# Wild_FDD_V1_1.net
KiCad netlist of a schematic drawn in Altium Designer
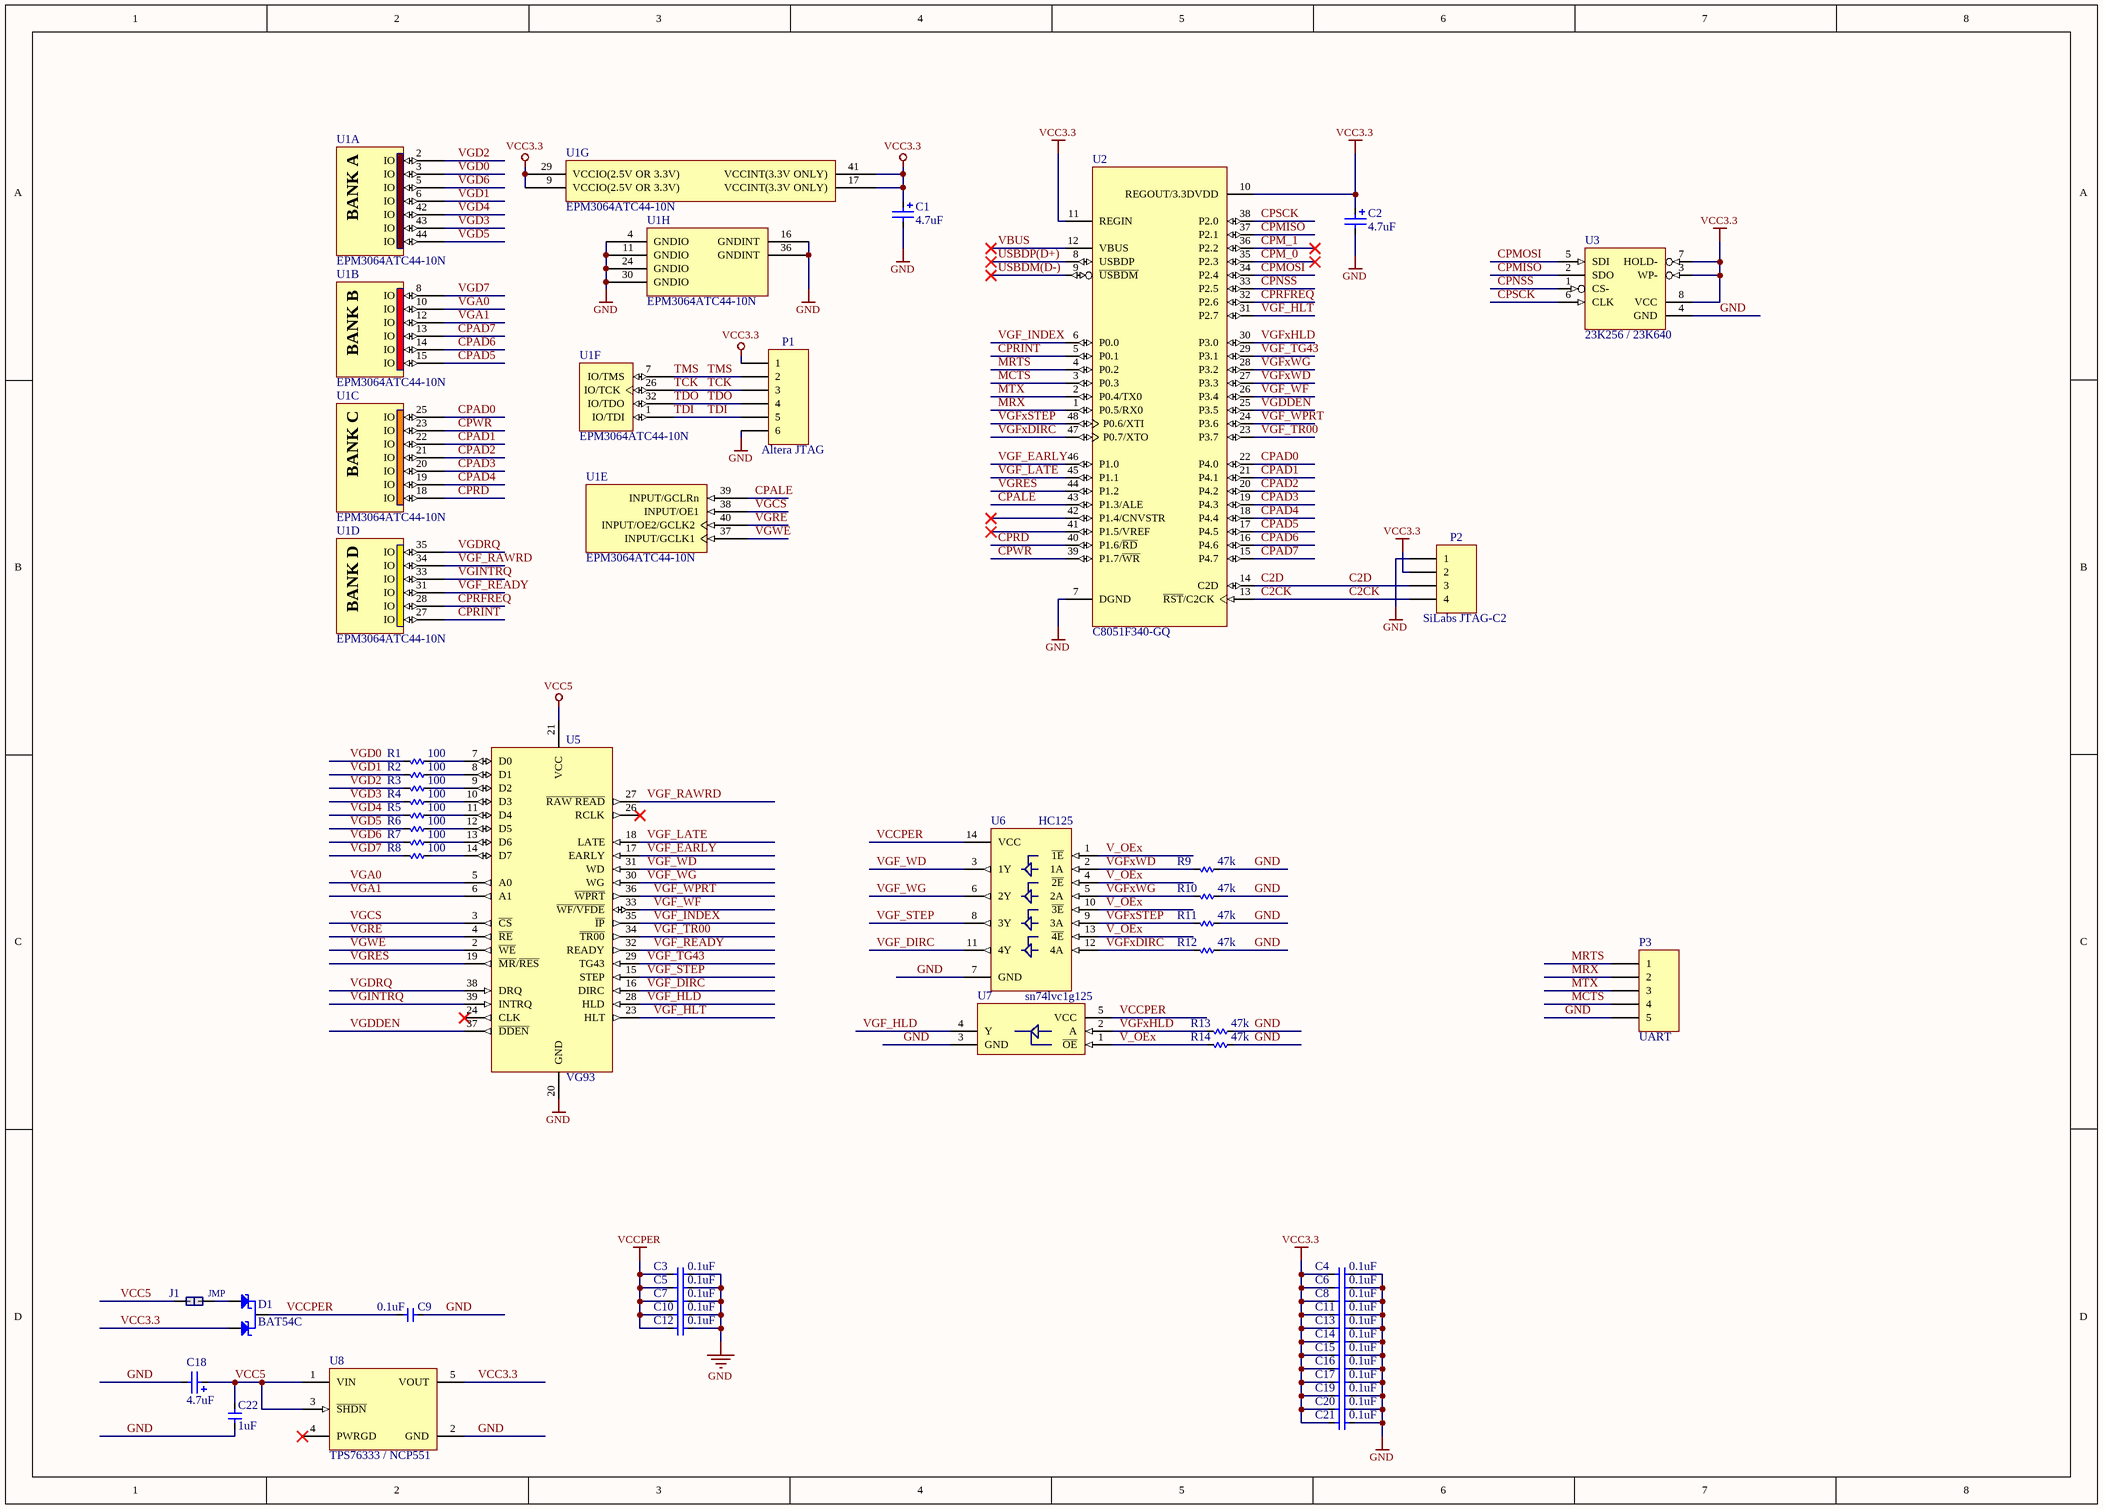
[diagram p0: Wild FDD V1.1.SchDoc]

(export (version "E")
  (design (tool "Eeschema 10.0.6"))
  (components
    (comp (ref "C1")
      (value "4.7uF")
      (footprint "CAP_TAN_B")
      (description "CAP TAN Size C")
      (libsource (lib "IntLib") (part "CAP_TAN_B"))
    )
    (comp (ref "C2")
      (value "4.7uF")
      (footprint "CAP_TAN_B")
      (description "CAP TAN Size C")
      (libsource (lib "IntLib") (part "CAP_TAN_B"))
    )
    (comp (ref "C3")
      (value "0.1uF")
      (footprint "R1005_CAP")
      (description "Capacitor")
      (fields
        (field (name "MANUFACTURER") "Generic Components")
        (field (name "Comment") "CAP")
        (field (name "PUBLISHER") "Altium Limited")
      )
      (libsource (lib "IntLib") (part "CAP"))
    )
    (comp (ref "C4")
      (value "0.1uF")
      (footprint "R1005_CAP")
      (description "Capacitor")
      (fields
        (field (name "MANUFACTURER") "Generic Components")
        (field (name "Comment") "CAP")
        (field (name "PUBLISHER") "Altium Limited")
      )
      (libsource (lib "IntLib") (part "CAP"))
    )
    (comp (ref "C5")
      (value "0.1uF")
      (footprint "R1005_CAP")
      (description "Capacitor")
      (fields
        (field (name "MANUFACTURER") "Generic Components")
        (field (name "Comment") "CAP")
        (field (name "PUBLISHER") "Altium Limited")
      )
      (libsource (lib "IntLib") (part "CAP"))
    )
    (comp (ref "C6")
      (value "0.1uF")
      (footprint "R1005_CAP")
      (description "Capacitor")
      (fields
        (field (name "MANUFACTURER") "Generic Components")
        (field (name "Comment") "CAP")
        (field (name "PUBLISHER") "Altium Limited")
      )
      (libsource (lib "IntLib") (part "CAP"))
    )
    (comp (ref "C7")
      (value "0.1uF")
      (footprint "R1005_CAP")
      (description "Capacitor")
      (fields
        (field (name "MANUFACTURER") "Generic Components")
        (field (name "Comment") "CAP")
        (field (name "PUBLISHER") "Altium Limited")
      )
      (libsource (lib "IntLib") (part "CAP"))
    )
    (comp (ref "C8")
      (value "0.1uF")
      (footprint "R1005_CAP")
      (description "Capacitor")
      (fields
        (field (name "MANUFACTURER") "Generic Components")
        (field (name "Comment") "CAP")
        (field (name "PUBLISHER") "Altium Limited")
      )
      (libsource (lib "IntLib") (part "CAP"))
    )
    (comp (ref "C9")
      (value "0.1uF")
      (footprint "R1005_CAP")
      (description "Capacitor")
      (fields
        (field (name "MANUFACTURER") "Generic Components")
        (field (name "Comment") "CAP")
        (field (name "PUBLISHER") "Altium Limited")
      )
      (libsource (lib "IntLib") (part "CAP"))
    )
    (comp (ref "C10")
      (value "0.1uF")
      (footprint "R1005_CAP")
      (description "Capacitor")
      (fields
        (field (name "MANUFACTURER") "Generic Components")
        (field (name "Comment") "CAP")
        (field (name "PUBLISHER") "Altium Limited")
      )
      (libsource (lib "IntLib") (part "CAP"))
    )
    (comp (ref "C11")
      (value "0.1uF")
      (footprint "R1005_CAP")
      (description "Capacitor")
      (fields
        (field (name "MANUFACTURER") "Generic Components")
        (field (name "Comment") "CAP")
        (field (name "PUBLISHER") "Altium Limited")
      )
      (libsource (lib "IntLib") (part "CAP"))
    )
    (comp (ref "C12")
      (value "0.1uF")
      (footprint "R1005_CAP")
      (description "Capacitor")
      (fields
        (field (name "MANUFACTURER") "Generic Components")
        (field (name "Comment") "CAP")
        (field (name "PUBLISHER") "Altium Limited")
      )
      (libsource (lib "IntLib") (part "CAP"))
    )
    (comp (ref "C13")
      (value "0.1uF")
      (footprint "R1005_CAP")
      (description "Capacitor")
      (fields
        (field (name "MANUFACTURER") "Generic Components")
        (field (name "Comment") "CAP")
        (field (name "PUBLISHER") "Altium Limited")
      )
      (libsource (lib "IntLib") (part "CAP"))
    )
    (comp (ref "C14")
      (value "0.1uF")
      (footprint "R1005_CAP")
      (description "Capacitor")
      (fields
        (field (name "MANUFACTURER") "Generic Components")
        (field (name "Comment") "CAP")
        (field (name "PUBLISHER") "Altium Limited")
      )
      (libsource (lib "IntLib") (part "CAP"))
    )
    (comp (ref "C15")
      (value "0.1uF")
      (footprint "R1005_CAP")
      (description "Capacitor")
      (fields
        (field (name "MANUFACTURER") "Generic Components")
        (field (name "Comment") "CAP")
        (field (name "PUBLISHER") "Altium Limited")
      )
      (libsource (lib "IntLib") (part "CAP"))
    )
    (comp (ref "C16")
      (value "0.1uF")
      (footprint "R1005_CAP")
      (description "Capacitor")
      (fields
        (field (name "MANUFACTURER") "Generic Components")
        (field (name "Comment") "CAP")
        (field (name "PUBLISHER") "Altium Limited")
      )
      (libsource (lib "IntLib") (part "CAP"))
    )
    (comp (ref "C17")
      (value "0.1uF")
      (footprint "R1005_CAP")
      (description "Capacitor")
      (fields
        (field (name "MANUFACTURER") "Generic Components")
        (field (name "Comment") "CAP")
        (field (name "PUBLISHER") "Altium Limited")
      )
      (libsource (lib "IntLib") (part "CAP"))
    )
    (comp (ref "C18")
      (value "4.7uF")
      (footprint "CAP_TAN_B")
      (description "CAP TAN Size C")
      (libsource (lib "IntLib") (part "CAP_TAN_B"))
    )
    (comp (ref "C19")
      (value "0.1uF")
      (footprint "R1005_CAP")
      (description "Capacitor")
      (fields
        (field (name "MANUFACTURER") "Generic Components")
        (field (name "Comment") "CAP")
        (field (name "PUBLISHER") "Altium Limited")
      )
      (libsource (lib "IntLib") (part "CAP"))
    )
    (comp (ref "C20")
      (value "0.1uF")
      (footprint "R1005_CAP")
      (description "Capacitor")
      (fields
        (field (name "MANUFACTURER") "Generic Components")
        (field (name "Comment") "CAP")
        (field (name "PUBLISHER") "Altium Limited")
      )
      (libsource (lib "IntLib") (part "CAP"))
    )
    (comp (ref "C21")
      (value "0.1uF")
      (footprint "R1005_CAP")
      (description "Capacitor")
      (fields
        (field (name "MANUFACTURER") "Generic Components")
        (field (name "Comment") "CAP")
        (field (name "PUBLISHER") "Altium Limited")
      )
      (libsource (lib "IntLib") (part "CAP"))
    )
    (comp (ref "C22")
      (value "1uF")
      (footprint "R1608_CAP")
      (description "Capacitor")
      (fields (field (name "MANUFACTURER") "Generic Components") (field (name "PUBLISHER") "Altium Limited"))
      (libsource (lib "IntLib") (part "CAP"))
    )
    (comp (ref "D1")
      (value "BAT54C")
      (footprint "SOT23-1")
      (description "Schottky Barrier Double Diode")
      (fields (field (name "PUBLISHER") "Altium Limited"))
      (libsource (lib "IntLib") (part "BAT54C"))
    )
    (comp (ref "J1")
      (value "JMP")
      (footprint "HDR1X2")
      (description "Crystal Oscillator")
      (fields
        (field (name "MANUFACTURER") "Generic Components")
        (field (name "Comment") "JUMPER")
        (field (name "PUBLISHER") "Altium Limited")
      )
      (libsource (lib "IntLib") (part "JUMPER"))
    )
    (comp (ref "P1")
      (value "Altera JTAG")
      (footprint "HDR1X6")
      (description "Header, 6-Pin")
      (fields (field (name "PUBLISHER") "Altium Limited"))
      (libsource (lib "Miscellaneous Connectors") (part "Header 6"))
    )
    (comp (ref "P2")
      (value "SiLabs JTAG-C2")
      (footprint "HDR1X4")
      (description "Header, 4-Pin")
      (fields (field (name "PUBLISHER") "Altium Limited"))
      (libsource (lib "Miscellaneous Connectors") (part "Header 4"))
    )
    (comp (ref "P3")
      (value "UART")
      (footprint "HDR1X5")
      (description "Header, 5-Pin")
      (fields (field (name "PUBLISHER") "Altium Limited"))
      (libsource (lib "Miscellaneous Connectors") (part "Header 5"))
    )
    (comp (ref "R1")
      (value "100")
      (footprint "R1608_RES")
      (description "Resistor")
      (fields
        (field (name "MANUFACTURER") "Generic Components")
        (field (name "Comment") "R")
        (field (name "PUBLISHER") "Altium Limited")
      )
      (libsource (lib "Passive_RC") (part "R"))
    )
    (comp (ref "R2")
      (value "100")
      (footprint "R1608_RES")
      (description "Resistor")
      (fields
        (field (name "MANUFACTURER") "Generic Components")
        (field (name "Comment") "R")
        (field (name "PUBLISHER") "Altium Limited")
      )
      (libsource (lib "Passive_RC") (part "R"))
    )
    (comp (ref "R3")
      (value "100")
      (footprint "R1608_RES")
      (description "Resistor")
      (fields
        (field (name "MANUFACTURER") "Generic Components")
        (field (name "Comment") "R")
        (field (name "PUBLISHER") "Altium Limited")
      )
      (libsource (lib "Passive_RC") (part "R"))
    )
    (comp (ref "R4")
      (value "100")
      (footprint "R1608_RES")
      (description "Resistor")
      (fields
        (field (name "MANUFACTURER") "Generic Components")
        (field (name "Comment") "R")
        (field (name "PUBLISHER") "Altium Limited")
      )
      (libsource (lib "Passive_RC") (part "R"))
    )
    (comp (ref "R5")
      (value "100")
      (footprint "R1608_RES")
      (description "Resistor")
      (fields
        (field (name "MANUFACTURER") "Generic Components")
        (field (name "Comment") "R")
        (field (name "PUBLISHER") "Altium Limited")
      )
      (libsource (lib "Passive_RC") (part "R"))
    )
    (comp (ref "R6")
      (value "100")
      (footprint "R1608_RES")
      (description "Resistor")
      (fields
        (field (name "MANUFACTURER") "Generic Components")
        (field (name "Comment") "R")
        (field (name "PUBLISHER") "Altium Limited")
      )
      (libsource (lib "Passive_RC") (part "R"))
    )
    (comp (ref "R7")
      (value "100")
      (footprint "R1608_RES")
      (description "Resistor")
      (fields
        (field (name "MANUFACTURER") "Generic Components")
        (field (name "Comment") "R")
        (field (name "PUBLISHER") "Altium Limited")
      )
      (libsource (lib "Passive_RC") (part "R"))
    )
    (comp (ref "R8")
      (value "100")
      (footprint "R1608_RES")
      (description "Resistor")
      (fields
        (field (name "MANUFACTURER") "Generic Components")
        (field (name "Comment") "R")
        (field (name "PUBLISHER") "Altium Limited")
      )
      (libsource (lib "Passive_RC") (part "R"))
    )
    (comp (ref "R9")
      (value "47k")
      (footprint "R1608_RES")
      (description "Resistor")
      (fields
        (field (name "MANUFACTURER") "Generic Components")
        (field (name "Comment") "R")
        (field (name "PUBLISHER") "Altium Limited")
      )
      (libsource (lib "Passive_RC") (part "R"))
    )
    (comp (ref "R10")
      (value "47k")
      (footprint "R1608_RES")
      (description "Resistor")
      (fields
        (field (name "MANUFACTURER") "Generic Components")
        (field (name "Comment") "R")
        (field (name "PUBLISHER") "Altium Limited")
      )
      (libsource (lib "Passive_RC") (part "R"))
    )
    (comp (ref "R11")
      (value "47k")
      (footprint "R1608_RES")
      (description "Resistor")
      (fields
        (field (name "MANUFACTURER") "Generic Components")
        (field (name "Comment") "R")
        (field (name "PUBLISHER") "Altium Limited")
      )
      (libsource (lib "Passive_RC") (part "R"))
    )
    (comp (ref "R12")
      (value "47k")
      (footprint "R1608_RES")
      (description "Resistor")
      (fields
        (field (name "MANUFACTURER") "Generic Components")
        (field (name "Comment") "R")
        (field (name "PUBLISHER") "Altium Limited")
      )
      (libsource (lib "Passive_RC") (part "R"))
    )
    (comp (ref "R13")
      (value "47k")
      (footprint "R1608_RES")
      (description "Resistor")
      (fields
        (field (name "MANUFACTURER") "Generic Components")
        (field (name "Comment") "R")
        (field (name "PUBLISHER") "Altium Limited")
      )
      (libsource (lib "Passive_RC") (part "R"))
    )
    (comp (ref "R14")
      (value "47k")
      (footprint "R1608_RES")
      (description "Resistor")
      (fields
        (field (name "MANUFACTURER") "Generic Components")
        (field (name "Comment") "R")
        (field (name "PUBLISHER") "Altium Limited")
      )
      (libsource (lib "Passive_RC") (part "R"))
    )
    (comp (ref "U1")
      (value "EPM3064ATC44-10N")
      (footprint "TQFP44_N")
      (description "MAX 3064A 3.3V CPLD, 34 IOs, 44-Pin Plastic TFQP, Commercial Temperature, Speed Grade 10, Pb-Free")
      (fields (field (name "PUBLISHER") "Altium Limited"))
      (libsource (lib "Altera MAX 3000A") (part "EPM3064ATC44-10N"))
    )
    (comp (ref "U2")
      (value "C8051F340-GQ")
      (footprint "TQFP48")
      (fields
        (field (name "DIGIKEYPARTNUMBER") "336-1298-ND")
        (field (name "PUBLISHER") "A and A System Co., Ltd.")
      )
      (libsource (lib "SiLabs Microcontroller 8-Bit 8051") (part "C8051F340-GQ"))
    )
    (comp (ref "U3")
      (value "FM25CLxx")
      (footprint "SO8-200")
      (description "FRAM SPI")
      (fields (field (name "TYPE") "23K256 / 23K640"))
      (libsource (lib "Memory") (part "FM25CLxx"))
    )
    (comp (ref "U5")
      (value "VG93")
      (footprint "DIP40_VG93")
      (description "Connector For Wild FDD")
      (libsource (lib "Robus") (part "VG93"))
    )
    (comp (ref "U6")
      (value "HC125")
      (footprint "SO14-150")
      (description "Quad buffer/line driver 3-state")
      (fields (field (name "PUBLISHER") "Altium Limited"))
      (libsource (lib "IntLib") (part "HC125"))
    )
    (comp (ref "U7")
      (value "sn74lvc1g125")
      (footprint "SOT23-5")
      (description "Single Buffer/Driver With Open-Drain Output")
      (fields (field (name "PUBLISHER") "Altium Limited"))
      (libsource (lib "IntLib") (part "sn74lvc1g125"))
    )
    (comp (ref "U8")
      (value "TPS76333 / NCP551")
      (footprint "SOT23-5D")
      (fields (field (name "PUBLISHER") "Altium Limited"))
      (libsource (lib "IntLib") (part "TPS76333"))
    )
  )
  (nets
    (net (code "1") (name "/C2CK") (class "Default")
      (node (ref "P2") (pin "4") (pinfunction "4_4") (pintype "passive"))
      (node (ref "U2") (pin "13") (pinfunction "~{RST}/C2CK_13") (pintype "input"))
    )
    (net (code "2") (name "/C2D") (class "Default")
      (node (ref "P2") (pin "3") (pinfunction "3_3") (pintype "passive"))
      (node (ref "U2") (pin "14") (pinfunction "C2D_14") (pintype "bidirectional"))
    )
    (net (code "3") (name "/CPAD0") (class "Default")
      (node (ref "U1") (pin "25") (pinfunction "IO_25") (pintype "bidirectional"))
      (node (ref "U2") (pin "22") (pinfunction "P4.0_22") (pintype "bidirectional"))
    )
    (net (code "4") (name "/CPAD1") (class "Default")
      (node (ref "U1") (pin "22") (pinfunction "IO_22") (pintype "bidirectional"))
      (node (ref "U2") (pin "21") (pinfunction "P4.1_21") (pintype "bidirectional"))
    )
    (net (code "5") (name "/CPAD2") (class "Default")
      (node (ref "U1") (pin "21") (pinfunction "IO_21") (pintype "bidirectional"))
      (node (ref "U2") (pin "20") (pinfunction "P4.2_20") (pintype "bidirectional"))
    )
    (net (code "6") (name "/CPAD3") (class "Default")
      (node (ref "U1") (pin "20") (pinfunction "IO_20") (pintype "bidirectional"))
      (node (ref "U2") (pin "19") (pinfunction "P4.3_19") (pintype "bidirectional"))
    )
    (net (code "7") (name "/CPAD4") (class "Default")
      (node (ref "U1") (pin "19") (pinfunction "IO_19") (pintype "bidirectional"))
      (node (ref "U2") (pin "18") (pinfunction "P4.4_18") (pintype "bidirectional"))
    )
    (net (code "8") (name "/CPAD5") (class "Default")
      (node (ref "U1") (pin "15") (pinfunction "IO_15") (pintype "bidirectional"))
      (node (ref "U2") (pin "17") (pinfunction "P4.5_17") (pintype "bidirectional"))
    )
    (net (code "9") (name "/CPAD6") (class "Default")
      (node (ref "U1") (pin "14") (pinfunction "IO_14") (pintype "bidirectional"))
      (node (ref "U2") (pin "16") (pinfunction "P4.6_16") (pintype "bidirectional"))
    )
    (net (code "10") (name "/CPAD7") (class "Default")
      (node (ref "U1") (pin "13") (pinfunction "IO_13") (pintype "bidirectional"))
      (node (ref "U2") (pin "15") (pinfunction "P4.7_15") (pintype "bidirectional"))
    )
    (net (code "11") (name "/CPALE") (class "Default")
      (node (ref "U1") (pin "39") (pinfunction "INPUT/GCLRn_39") (pintype "input"))
      (node (ref "U2") (pin "43") (pinfunction "P1.3/ALE_43") (pintype "bidirectional"))
    )
    (net (code "12") (name "/CPMISO") (class "Default")
      (node (ref "U2") (pin "37") (pinfunction "P2.1_37") (pintype "bidirectional"))
      (node (ref "U3") (pin "2") (pinfunction "SDO_2") (pintype "passive"))
    )
    (net (code "13") (name "/CPMOSI") (class "Default")
      (node (ref "U2") (pin "34") (pinfunction "P2.4_34") (pintype "bidirectional"))
      (node (ref "U3") (pin "5") (pinfunction "SDI_5") (pintype "input"))
    )
    (net (code "14") (name "/CPM_0") (class "Default")
      (node (ref "U2") (pin "35") (pinfunction "P2.3_35") (pintype "bidirectional+no_connect"))
    )
    (net (code "15") (name "/CPM_1") (class "Default")
      (node (ref "U2") (pin "36") (pinfunction "P2.2_36") (pintype "bidirectional+no_connect"))
    )
    (net (code "16") (name "/CPNSS") (class "Default")
      (node (ref "U2") (pin "33") (pinfunction "P2.5_33") (pintype "bidirectional"))
      (node (ref "U3") (pin "1") (pinfunction "CS-_1") (pintype "input"))
    )
    (net (code "17") (name "/CPRD") (class "Default")
      (node (ref "U1") (pin "18") (pinfunction "IO_18") (pintype "bidirectional"))
      (node (ref "U2") (pin "40") (pinfunction "P1.6/~{RD}_40") (pintype "bidirectional"))
    )
    (net (code "18") (name "/CPRFREQ") (class "Default")
      (node (ref "U1") (pin "28") (pinfunction "IO_28") (pintype "bidirectional"))
      (node (ref "U2") (pin "32") (pinfunction "P2.6_32") (pintype "bidirectional"))
    )
    (net (code "19") (name "/CPRINT") (class "Default")
      (node (ref "U1") (pin "27") (pinfunction "IO_27") (pintype "bidirectional"))
      (node (ref "U2") (pin "5") (pinfunction "P0.1_5") (pintype "bidirectional"))
    )
    (net (code "20") (name "/CPSCK") (class "Default")
      (node (ref "U2") (pin "38") (pinfunction "P2.0_38") (pintype "bidirectional"))
      (node (ref "U3") (pin "6") (pinfunction "CLK_6") (pintype "input"))
    )
    (net (code "21") (name "/CPWR") (class "Default")
      (node (ref "U1") (pin "23") (pinfunction "IO_23") (pintype "bidirectional"))
      (node (ref "U2") (pin "39") (pinfunction "P1.7/~{WR}_39") (pintype "bidirectional"))
    )
    (net (code "22") (name "/MCTS") (class "Default")
      (node (ref "P3") (pin "4") (pinfunction "4_4") (pintype "passive"))
      (node (ref "U2") (pin "3") (pinfunction "P0.3_3") (pintype "bidirectional"))
    )
    (net (code "23") (name "/MRTS") (class "Default")
      (node (ref "P3") (pin "1") (pinfunction "1_1") (pintype "passive"))
      (node (ref "U2") (pin "4") (pinfunction "P0.2_4") (pintype "bidirectional"))
    )
    (net (code "24") (name "/MRX") (class "Default")
      (node (ref "P3") (pin "2") (pinfunction "2_2") (pintype "passive"))
      (node (ref "U2") (pin "1") (pinfunction "P0.5/RX0_1") (pintype "bidirectional"))
    )
    (net (code "25") (name "/MTX") (class "Default")
      (node (ref "P3") (pin "3") (pinfunction "3_3") (pintype "passive"))
      (node (ref "U2") (pin "2") (pinfunction "P0.4/TX0_2") (pintype "bidirectional"))
    )
    (net (code "26") (name "/TCK") (class "Default")
      (node (ref "P1") (pin "3") (pinfunction "3_3") (pintype "passive"))
      (node (ref "U1") (pin "26") (pinfunction "IO/TCK_26") (pintype "bidirectional"))
    )
    (net (code "27") (name "/TDI") (class "Default")
      (node (ref "P1") (pin "5") (pinfunction "5_5") (pintype "passive"))
      (node (ref "U1") (pin "1") (pinfunction "IO/TDI_1") (pintype "bidirectional"))
    )
    (net (code "28") (name "/TDO") (class "Default")
      (node (ref "P1") (pin "4") (pinfunction "4_4") (pintype "passive"))
      (node (ref "U1") (pin "32") (pinfunction "IO/TDO_32") (pintype "bidirectional"))
    )
    (net (code "29") (name "/TMS") (class "Default")
      (node (ref "P1") (pin "2") (pinfunction "2_2") (pintype "passive"))
      (node (ref "U1") (pin "7") (pinfunction "IO/TMS_7") (pintype "bidirectional"))
    )
    (net (code "30") (name "/USBDM(D-)") (class "Default")
      (node (ref "U2") (pin "9") (pinfunction "~{USBDM}_9") (pintype "bidirectional+no_connect"))
    )
    (net (code "31") (name "/USBDP(D+)") (class "Default")
      (node (ref "U2") (pin "8") (pinfunction "USBDP_8") (pintype "bidirectional+no_connect"))
    )
    (net (code "32") (name "/VBUS") (class "Default")
      (node (ref "U2") (pin "12") (pinfunction "VBUS_12") (pintype "power_in+no_connect"))
    )
    (net (code "33") (name "/VGA0") (class "Default")
      (node (ref "U1") (pin "10") (pinfunction "IO_10") (pintype "bidirectional"))
      (node (ref "U5") (pin "5") (pinfunction "A0_5") (pintype "output"))
    )
    (net (code "34") (name "/VGA1") (class "Default")
      (node (ref "U1") (pin "12") (pinfunction "IO_12") (pintype "bidirectional"))
      (node (ref "U5") (pin "6") (pinfunction "A1_6") (pintype "output"))
    )
    (net (code "35") (name "/VGCS") (class "Default")
      (node (ref "U1") (pin "38") (pinfunction "INPUT/OE1_38") (pintype "input"))
      (node (ref "U5") (pin "3") (pinfunction "~{CS}_3") (pintype "output"))
    )
    (net (code "36") (name "/VGD0") (class "Default")
      (node (ref "R1") (pin "2") (pinfunction "2_2") (pintype "passive"))
      (node (ref "U1") (pin "3") (pinfunction "IO_3") (pintype "bidirectional"))
    )
    (net (code "37") (name "/VGD1") (class "Default")
      (node (ref "R2") (pin "2") (pinfunction "2_2") (pintype "passive"))
      (node (ref "U1") (pin "6") (pinfunction "IO_6") (pintype "bidirectional"))
    )
    (net (code "38") (name "/VGD2") (class "Default")
      (node (ref "R3") (pin "2") (pinfunction "2_2") (pintype "passive"))
      (node (ref "U1") (pin "2") (pinfunction "IO_2") (pintype "bidirectional"))
    )
    (net (code "39") (name "/VGD3") (class "Default")
      (node (ref "R4") (pin "2") (pinfunction "2_2") (pintype "passive"))
      (node (ref "U1") (pin "43") (pinfunction "IO_43") (pintype "bidirectional"))
    )
    (net (code "40") (name "/VGD4") (class "Default")
      (node (ref "R5") (pin "2") (pinfunction "2_2") (pintype "passive"))
      (node (ref "U1") (pin "42") (pinfunction "IO_42") (pintype "bidirectional"))
    )
    (net (code "41") (name "/VGD5") (class "Default")
      (node (ref "R6") (pin "2") (pinfunction "2_2") (pintype "passive"))
      (node (ref "U1") (pin "44") (pinfunction "IO_44") (pintype "bidirectional"))
    )
    (net (code "42") (name "/VGD6") (class "Default")
      (node (ref "R7") (pin "2") (pinfunction "2_2") (pintype "passive"))
      (node (ref "U1") (pin "5") (pinfunction "IO_5") (pintype "bidirectional"))
    )
    (net (code "43") (name "/VGD7") (class "Default")
      (node (ref "R8") (pin "2") (pinfunction "2_2") (pintype "passive"))
      (node (ref "U1") (pin "8") (pinfunction "IO_8") (pintype "bidirectional"))
    )
    (net (code "44") (name "/VGDDEN") (class "Default")
      (node (ref "U2") (pin "25") (pinfunction "P3.5_25") (pintype "bidirectional"))
      (node (ref "U5") (pin "37") (pinfunction "~{DDEN}_37") (pintype "output"))
    )
    (net (code "45") (name "/VGDRQ") (class "Default")
      (node (ref "U1") (pin "35") (pinfunction "IO_35") (pintype "bidirectional"))
      (node (ref "U5") (pin "38") (pinfunction "DRQ_38") (pintype "input"))
    )
    (net (code "46") (name "/VGF_DIRC") (class "Default")
      (node (ref "U5") (pin "16") (pinfunction "DIRC_16") (pintype "input"))
      (node (ref "U6") (pin "11") (pinfunction "4Y_11") (pintype "output"))
    )
    (net (code "47") (name "/VGF_EARLY") (class "Default")
      (node (ref "U2") (pin "46") (pinfunction "P1.0_46") (pintype "bidirectional"))
      (node (ref "U5") (pin "17") (pinfunction "EARLY_17") (pintype "input"))
    )
    (net (code "48") (name "/VGF_HLD") (class "Default")
      (node (ref "U5") (pin "28") (pinfunction "HLD_28") (pintype "input"))
      (node (ref "U7") (pin "4") (pinfunction "Y_4") (pintype "open_collector"))
    )
    (net (code "49") (name "/VGF_HLT") (class "Default")
      (node (ref "U2") (pin "31") (pinfunction "P2.7_31") (pintype "bidirectional"))
      (node (ref "U5") (pin "23") (pinfunction "HLT_23") (pintype "output"))
    )
    (net (code "50") (name "/VGF_INDEX") (class "Default")
      (node (ref "U2") (pin "6") (pinfunction "P0.0_6") (pintype "bidirectional"))
      (node (ref "U5") (pin "35") (pinfunction "~{IP}_35") (pintype "output"))
    )
    (net (code "51") (name "/VGF_LATE") (class "Default")
      (node (ref "U2") (pin "45") (pinfunction "P1.1_45") (pintype "bidirectional"))
      (node (ref "U5") (pin "18") (pinfunction "LATE_18") (pintype "input"))
    )
    (net (code "52") (name "/VGF_RAWRD") (class "Default")
      (node (ref "U1") (pin "34") (pinfunction "IO_34") (pintype "bidirectional"))
      (node (ref "U5") (pin "27") (pinfunction "~{RAW_READ}_27") (pintype "output"))
    )
    (net (code "53") (name "/VGF_READY") (class "Default")
      (node (ref "U1") (pin "31") (pinfunction "IO_31") (pintype "bidirectional"))
      (node (ref "U5") (pin "32") (pinfunction "READY_32") (pintype "output"))
    )
    (net (code "54") (name "/VGF_STEP") (class "Default")
      (node (ref "U5") (pin "15") (pinfunction "STEP_15") (pintype "input"))
      (node (ref "U6") (pin "8") (pinfunction "3Y_8") (pintype "output"))
    )
    (net (code "55") (name "/VGF_TG43") (class "Default")
      (node (ref "U2") (pin "29") (pinfunction "P3.1_29") (pintype "bidirectional"))
      (node (ref "U5") (pin "29") (pinfunction "TG43_29") (pintype "input"))
    )
    (net (code "56") (name "/VGF_TR00") (class "Default")
      (node (ref "U2") (pin "23") (pinfunction "P3.7_23") (pintype "bidirectional"))
      (node (ref "U5") (pin "34") (pinfunction "~{TR00}_34") (pintype "output"))
    )
    (net (code "57") (name "/VGF_WD") (class "Default")
      (node (ref "U5") (pin "31") (pinfunction "WD_31") (pintype "input"))
      (node (ref "U6") (pin "3") (pinfunction "1Y_3") (pintype "output"))
    )
    (net (code "58") (name "/VGF_WF") (class "Default")
      (node (ref "U2") (pin "26") (pinfunction "P3.4_26") (pintype "bidirectional"))
      (node (ref "U5") (pin "33") (pinfunction "~{WF/VFDE}_33") (pintype "bidirectional"))
    )
    (net (code "59") (name "/VGF_WG") (class "Default")
      (node (ref "U5") (pin "30") (pinfunction "WG_30") (pintype "input"))
      (node (ref "U6") (pin "6") (pinfunction "2Y_6") (pintype "output"))
    )
    (net (code "60") (name "/VGF_WPRT") (class "Default")
      (node (ref "U2") (pin "24") (pinfunction "P3.6_24") (pintype "bidirectional"))
      (node (ref "U5") (pin "36") (pinfunction "~{WPRT}_36") (pintype "output"))
    )
    (net (code "61") (name "/VGFxDIRC") (class "Default")
      (node (ref "R12") (pin "2") (pinfunction "2_2") (pintype "passive"))
      (node (ref "U2") (pin "47") (pinfunction "P0.7/XTO_47") (pintype "bidirectional"))
      (node (ref "U6") (pin "12") (pinfunction "4A_12") (pintype "input"))
    )
    (net (code "62") (name "/VGFxHLD") (class "Default")
      (node (ref "R13") (pin "2") (pinfunction "2_2") (pintype "passive"))
      (node (ref "U2") (pin "30") (pinfunction "P3.0_30") (pintype "bidirectional"))
      (node (ref "U7") (pin "2") (pinfunction "A_2") (pintype "input"))
    )
    (net (code "63") (name "/VGFxSTEP") (class "Default")
      (node (ref "R11") (pin "2") (pinfunction "2_2") (pintype "passive"))
      (node (ref "U2") (pin "48") (pinfunction "P0.6/XTI_48") (pintype "bidirectional"))
      (node (ref "U6") (pin "9") (pinfunction "3A_9") (pintype "input"))
    )
    (net (code "64") (name "/VGFxWD") (class "Default")
      (node (ref "R9") (pin "2") (pinfunction "2_2") (pintype "passive"))
      (node (ref "U2") (pin "27") (pinfunction "P3.3_27") (pintype "bidirectional"))
      (node (ref "U6") (pin "2") (pinfunction "1A_2") (pintype "input"))
    )
    (net (code "65") (name "/VGFxWG") (class "Default")
      (node (ref "R10") (pin "2") (pinfunction "2_2") (pintype "passive"))
      (node (ref "U2") (pin "28") (pinfunction "P3.2_28") (pintype "bidirectional"))
      (node (ref "U6") (pin "5") (pinfunction "2A_5") (pintype "input"))
    )
    (net (code "66") (name "/VGINTRQ") (class "Default")
      (node (ref "U1") (pin "33") (pinfunction "IO_33") (pintype "bidirectional"))
      (node (ref "U5") (pin "39") (pinfunction "INTRQ_39") (pintype "input"))
    )
    (net (code "67") (name "/VGRE") (class "Default")
      (node (ref "U1") (pin "40") (pinfunction "INPUT/OE2/GCLK2_40") (pintype "input"))
      (node (ref "U5") (pin "4") (pinfunction "~{RE}_4") (pintype "output"))
    )
    (net (code "68") (name "/VGRES") (class "Default")
      (node (ref "U2") (pin "44") (pinfunction "P1.2_44") (pintype "bidirectional"))
      (node (ref "U5") (pin "19") (pinfunction "~{MR}/~{RES}_19") (pintype "output"))
    )
    (net (code "69") (name "/VGWE") (class "Default")
      (node (ref "U1") (pin "37") (pinfunction "INPUT/GCLK1_37") (pintype "input"))
      (node (ref "U5") (pin "2") (pinfunction "~{WE}_2") (pintype "output"))
    )
    (net (code "70") (name "/V_OEx") (class "Default")
      (node (ref "R14") (pin "2") (pinfunction "2_2") (pintype "passive"))
      (node (ref "U6") (pin "1") (pinfunction "~{1E}_1") (pintype "input"))
      (node (ref "U6") (pin "10") (pinfunction "~{3E}_10") (pintype "input"))
      (node (ref "U6") (pin "13") (pinfunction "~{4E}_13") (pintype "input"))
      (node (ref "U6") (pin "4") (pinfunction "~{2E}_4") (pintype "input"))
      (node (ref "U7") (pin "1") (pinfunction "~{OE}_1") (pintype "input"))
    )
    (net (code "71") (name "GND") (class "Default")
      (node (ref "C1") (pin "2") (pinfunction "2_2") (pintype "passive"))
      (node (ref "C10") (pin "1") (pinfunction "1_1") (pintype "passive"))
      (node (ref "C11") (pin "1") (pinfunction "1_1") (pintype "passive"))
      (node (ref "C12") (pin "1") (pinfunction "1_1") (pintype "passive"))
      (node (ref "C13") (pin "1") (pinfunction "1_1") (pintype "passive"))
      (node (ref "C14") (pin "1") (pinfunction "1_1") (pintype "passive"))
      (node (ref "C15") (pin "1") (pinfunction "1_1") (pintype "passive"))
      (node (ref "C16") (pin "1") (pinfunction "1_1") (pintype "passive"))
      (node (ref "C17") (pin "1") (pinfunction "1_1") (pintype "passive"))
      (node (ref "C18") (pin "2") (pinfunction "2_2") (pintype "passive"))
      (node (ref "C19") (pin "1") (pinfunction "1_1") (pintype "passive"))
      (node (ref "C2") (pin "2") (pinfunction "2_2") (pintype "passive"))
      (node (ref "C20") (pin "1") (pinfunction "1_1") (pintype "passive"))
      (node (ref "C21") (pin "1") (pinfunction "1_1") (pintype "passive"))
      (node (ref "C22") (pin "1") (pinfunction "1_1") (pintype "passive"))
      (node (ref "C3") (pin "1") (pinfunction "1_1") (pintype "passive"))
      (node (ref "C4") (pin "1") (pinfunction "1_1") (pintype "passive"))
      (node (ref "C5") (pin "1") (pinfunction "1_1") (pintype "passive"))
      (node (ref "C6") (pin "1") (pinfunction "1_1") (pintype "passive"))
      (node (ref "C7") (pin "1") (pinfunction "1_1") (pintype "passive"))
      (node (ref "C8") (pin "1") (pinfunction "1_1") (pintype "passive"))
      (node (ref "C9") (pin "1") (pinfunction "1_1") (pintype "passive"))
      (node (ref "P1") (pin "6") (pinfunction "6_6") (pintype "passive"))
      (node (ref "P2") (pin "1") (pinfunction "1_1") (pintype "passive"))
      (node (ref "P3") (pin "5") (pinfunction "5_5") (pintype "passive"))
      (node (ref "R10") (pin "1") (pinfunction "1_1") (pintype "passive"))
      (node (ref "R11") (pin "1") (pinfunction "1_1") (pintype "passive"))
      (node (ref "R12") (pin "1") (pinfunction "1_1") (pintype "passive"))
      (node (ref "R13") (pin "1") (pinfunction "1_1") (pintype "passive"))
      (node (ref "R14") (pin "1") (pinfunction "1_1") (pintype "passive"))
      (node (ref "R9") (pin "1") (pinfunction "1_1") (pintype "passive"))
      (node (ref "U1") (pin "11") (pinfunction "GNDIO_11") (pintype "power_in"))
      (node (ref "U1") (pin "16") (pinfunction "GNDINT_16") (pintype "power_in"))
      (node (ref "U1") (pin "24") (pinfunction "GNDIO_24") (pintype "power_in"))
      (node (ref "U1") (pin "30") (pinfunction "GNDIO_30") (pintype "power_in"))
      (node (ref "U1") (pin "36") (pinfunction "GNDINT_36") (pintype "power_in"))
      (node (ref "U1") (pin "4") (pinfunction "GNDIO_4") (pintype "power_in"))
      (node (ref "U2") (pin "7") (pinfunction "DGND_7") (pintype "power_in"))
      (node (ref "U3") (pin "4") (pinfunction "GND_4") (pintype "power_in"))
      (node (ref "U5") (pin "20") (pinfunction "GND_20") (pintype "power_in"))
      (node (ref "U6") (pin "7") (pinfunction "GND_7") (pintype "power_in"))
      (node (ref "U7") (pin "3") (pinfunction "GND_3") (pintype "power_in"))
      (node (ref "U8") (pin "2") (pinfunction "GND_2") (pintype "power_in"))
    )
    (net (code "72") (name "Net-(D1-A1)") (class "Default")
      (node (ref "D1") (pin "1") (pinfunction "A1_1") (pintype "passive"))
      (node (ref "J1") (pin "2") (pinfunction "OSC2_2") (pintype "passive"))
    )
    (net (code "73") (name "Net-(U5-D0)") (class "Default")
      (node (ref "R1") (pin "1") (pinfunction "1_1") (pintype "passive"))
      (node (ref "U5") (pin "7") (pinfunction "D0_7") (pintype "bidirectional"))
    )
    (net (code "74") (name "Net-(U5-D1)") (class "Default")
      (node (ref "R2") (pin "1") (pinfunction "1_1") (pintype "passive"))
      (node (ref "U5") (pin "8") (pinfunction "D1_8") (pintype "bidirectional"))
    )
    (net (code "75") (name "Net-(U5-D2)") (class "Default")
      (node (ref "R3") (pin "1") (pinfunction "1_1") (pintype "passive"))
      (node (ref "U5") (pin "9") (pinfunction "D2_9") (pintype "bidirectional"))
    )
    (net (code "76") (name "Net-(U5-D3)") (class "Default")
      (node (ref "R4") (pin "1") (pinfunction "1_1") (pintype "passive"))
      (node (ref "U5") (pin "10") (pinfunction "D3_10") (pintype "bidirectional"))
    )
    (net (code "77") (name "Net-(U5-D4)") (class "Default")
      (node (ref "R5") (pin "1") (pinfunction "1_1") (pintype "passive"))
      (node (ref "U5") (pin "11") (pinfunction "D4_11") (pintype "bidirectional"))
    )
    (net (code "78") (name "Net-(U5-D5)") (class "Default")
      (node (ref "R6") (pin "1") (pinfunction "1_1") (pintype "passive"))
      (node (ref "U5") (pin "12") (pinfunction "D5_12") (pintype "bidirectional"))
    )
    (net (code "79") (name "Net-(U5-D6)") (class "Default")
      (node (ref "R7") (pin "1") (pinfunction "1_1") (pintype "passive"))
      (node (ref "U5") (pin "13") (pinfunction "D6_13") (pintype "bidirectional"))
    )
    (net (code "80") (name "Net-(U5-D7)") (class "Default")
      (node (ref "R8") (pin "1") (pinfunction "1_1") (pintype "passive"))
      (node (ref "U5") (pin "14") (pinfunction "D7_14") (pintype "bidirectional"))
    )
    (net (code "81") (name "VCC3.3") (class "Default")
      (node (ref "C1") (pin "1") (pinfunction "1_1") (pintype "passive"))
      (node (ref "C11") (pin "2") (pinfunction "2_2") (pintype "passive"))
      (node (ref "C13") (pin "2") (pinfunction "2_2") (pintype "passive"))
      (node (ref "C14") (pin "2") (pinfunction "2_2") (pintype "passive"))
      (node (ref "C15") (pin "2") (pinfunction "2_2") (pintype "passive"))
      (node (ref "C16") (pin "2") (pinfunction "2_2") (pintype "passive"))
      (node (ref "C17") (pin "2") (pinfunction "2_2") (pintype "passive"))
      (node (ref "C19") (pin "2") (pinfunction "2_2") (pintype "passive"))
      (node (ref "C2") (pin "1") (pinfunction "1_1") (pintype "passive"))
      (node (ref "C20") (pin "2") (pinfunction "2_2") (pintype "passive"))
      (node (ref "C21") (pin "2") (pinfunction "2_2") (pintype "passive"))
      (node (ref "C4") (pin "2") (pinfunction "2_2") (pintype "passive"))
      (node (ref "C6") (pin "2") (pinfunction "2_2") (pintype "passive"))
      (node (ref "C8") (pin "2") (pinfunction "2_2") (pintype "passive"))
      (node (ref "D1") (pin "2") (pinfunction "A2_2") (pintype "passive"))
      (node (ref "P1") (pin "1") (pinfunction "1_1") (pintype "passive"))
      (node (ref "P2") (pin "2") (pinfunction "2_2") (pintype "passive"))
      (node (ref "U1") (pin "17") (pinfunction "VCCINT(3.3V_ONLY)_17") (pintype "power_in"))
      (node (ref "U1") (pin "29") (pinfunction "VCCIO(2.5V_OR_3.3V)_29") (pintype "power_in"))
      (node (ref "U1") (pin "41") (pinfunction "VCCINT(3.3V_ONLY)_41") (pintype "power_in"))
      (node (ref "U1") (pin "9") (pinfunction "VCCIO(2.5V_OR_3.3V)_9") (pintype "power_in"))
      (node (ref "U2") (pin "10") (pinfunction "REGOUT/3.3DVDD_10") (pintype "power_in"))
      (node (ref "U2") (pin "11") (pinfunction "REGIN_11") (pintype "power_in"))
      (node (ref "U3") (pin "3") (pinfunction "WP-_3") (pintype "input"))
      (node (ref "U3") (pin "7") (pinfunction "HOLD-_7") (pintype "input"))
      (node (ref "U3") (pin "8") (pinfunction "VCC_8") (pintype "power_in"))
      (node (ref "U8") (pin "5") (pinfunction "VOUT_5") (pintype "power_in"))
    )
    (net (code "82") (name "VCC5") (class "Default")
      (node (ref "C18") (pin "1") (pinfunction "1_1") (pintype "passive"))
      (node (ref "C22") (pin "2") (pinfunction "2_2") (pintype "passive"))
      (node (ref "J1") (pin "1") (pinfunction "OSC1_1") (pintype "passive"))
      (node (ref "U5") (pin "21") (pinfunction "VCC_21") (pintype "power_in"))
      (node (ref "U8") (pin "1") (pinfunction "VIN_1") (pintype "power_in"))
      (node (ref "U8") (pin "3") (pinfunction "~{SHDN}_3") (pintype "input"))
    )
    (net (code "83") (name "VCCPER") (class "Default")
      (node (ref "C10") (pin "2") (pinfunction "2_2") (pintype "passive"))
      (node (ref "C12") (pin "2") (pinfunction "2_2") (pintype "passive"))
      (node (ref "C3") (pin "2") (pinfunction "2_2") (pintype "passive"))
      (node (ref "C5") (pin "2") (pinfunction "2_2") (pintype "passive"))
      (node (ref "C7") (pin "2") (pinfunction "2_2") (pintype "passive"))
      (node (ref "C9") (pin "2") (pinfunction "2_2") (pintype "passive"))
      (node (ref "D1") (pin "3") (pinfunction "K_3") (pintype "passive"))
      (node (ref "U6") (pin "14") (pinfunction "VCC_14") (pintype "power_in"))
      (node (ref "U7") (pin "5") (pinfunction "VCC_5") (pintype "power_in"))
    )
    (net (code "84") (name "unconnected-(U2-P1.4{slash}CNVSTR-Pad42)") (class "Default")
      (node (ref "U2") (pin "42") (pinfunction "P1.4/CNVSTR_42") (pintype "bidirectional+no_connect"))
    )
    (net (code "85") (name "unconnected-(U2-P1.5{slash}VREF-Pad41)") (class "Default")
      (node (ref "U2") (pin "41") (pinfunction "P1.5/VREF_41") (pintype "bidirectional+no_connect"))
    )
    (net (code "86") (name "unconnected-(U5-CLK-Pad24)") (class "Default")
      (node (ref "U5") (pin "24") (pinfunction "CLK_24") (pintype "output+no_connect"))
    )
    (net (code "87") (name "unconnected-(U5-RCLK-Pad26)") (class "Default")
      (node (ref "U5") (pin "26") (pinfunction "RCLK_26") (pintype "output+no_connect"))
    )
    (net (code "88") (name "unconnected-(U8-PWRGD-Pad4)") (class "Default")
      (node (ref "U8") (pin "4") (pinfunction "PWRGD_4") (pintype "power_in+no_connect"))
    )
  )
)
